# 5v-buck-regulator.net
KiCad netlist of a schematic drawn in EAGLE
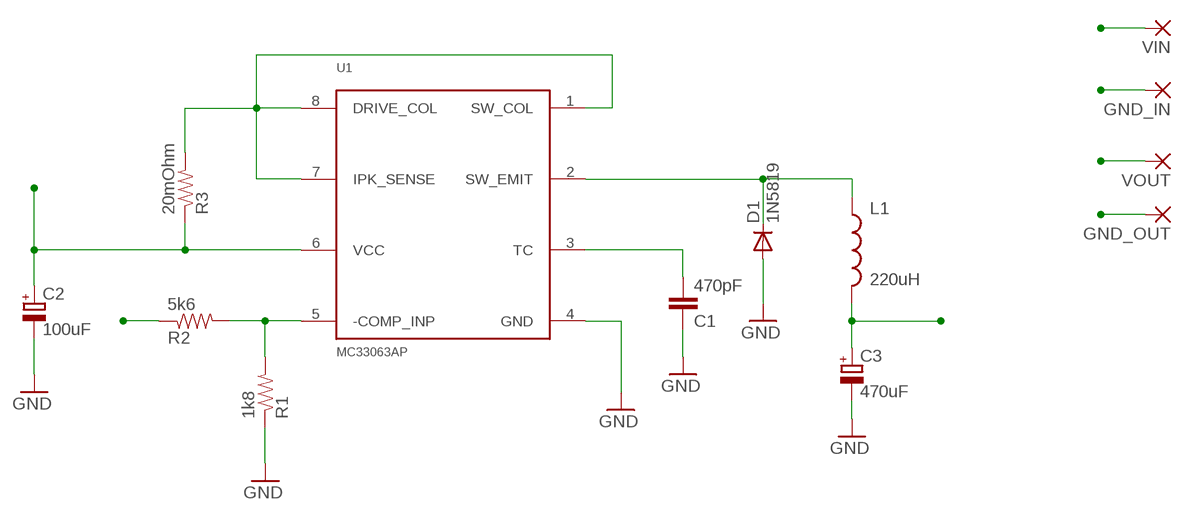
[diagram p0: schematic, sheet 1]

(export (version "E")
  (design (tool "Eeschema 10.0.6"))
  (components
    (comp (ref "C1")
      (value "470pF")
      (footprint "eagle-import:0805")
      (libsource (lib "eagle-import") (part "CAP0805"))
    )
    (comp (ref "C2")
      (value "100uF")
      (footprint "eagle-import:PANASONIC_C")
      (libsource (lib "eagle-import") (part "CPOL-EUC"))
    )
    (comp (ref "C3")
      (value "470uF")
      (footprint "eagle-import:PANASONIC_D")
      (libsource (lib "eagle-import") (part "CPOL-EUD"))
    )
    (comp (ref "D1")
      (value "1N5819")
      (footprint "eagle-import:SOD123")
      (libsource (lib "eagle-import") (part "MBR0520LT"))
    )
    (comp (ref "GND_IN")
      (value "WIREPAD2,54/0,8")
      (footprint "eagle-import:2,54_0,8")
      (libsource (lib "eagle-import") (part "WIREPAD2,54/0,8"))
    )
    (comp (ref "GND_OUT")
      (value "WIREPAD2,54/0,8")
      (footprint "eagle-import:2,54_0,8")
      (libsource (lib "eagle-import") (part "WIREPAD2,54/0,8"))
    )
    (comp (ref "L1")
      (value "220uH")
      (footprint "eagle-import:B82462G")
      (libsource (lib "eagle-import") (part "INDUCTOR-B82462G"))
    )
    (comp (ref "R1")
      (value "1k8")
      (footprint "eagle-import:0805")
      (libsource (lib "eagle-import") (part "RESISTOR0805-RES"))
    )
    (comp (ref "R2")
      (value "5k6")
      (footprint "eagle-import:0805")
      (libsource (lib "eagle-import") (part "RESISTOR0805-RES"))
    )
    (comp (ref "R3")
      (value "20mOhm")
      (footprint "eagle-import:R2010")
      (libsource (lib "eagle-import") (part "RESISTOR2010"))
    )
    (comp (ref "U1")
      (value "MC33063AP")
      (footprint "eagle-import:SOIC-8")
      (libsource (lib "eagle-import") (part "MC33063AMC34063A"))
    )
    (comp (ref "VIN")
      (value "WIREPAD2,54/0,8")
      (footprint "eagle-import:2,54_0,8")
      (libsource (lib "eagle-import") (part "WIREPAD2,54/0,8"))
    )
    (comp (ref "VOUT")
      (value "WIREPAD2,54/0,8")
      (footprint "eagle-import:2,54_0,8")
      (libsource (lib "eagle-import") (part "WIREPAD2,54/0,8"))
    )
  )
  (nets
    (net (code "1") (name "/VIN") (class "Default")
      (node (ref "C2") (pin "+") (pinfunction "+_+") (pintype "passive"))
      (node (ref "R3") (pin "1") (pinfunction "1_1") (pintype "passive"))
      (node (ref "U1") (pin "6") (pinfunction "VCC_6") (pintype "bidirectional"))
      (node (ref "VIN") (pin "1") (pinfunction "P_1") (pintype "passive"))
    )
    (net (code "2") (name "/VOUT") (class "Default")
      (node (ref "C3") (pin "+") (pinfunction "+_+") (pintype "passive"))
      (node (ref "L1") (pin "P$2") (pinfunction "2_P$2") (pintype "passive"))
      (node (ref "R2") (pin "1") (pinfunction "1_1") (pintype "passive"))
      (node (ref "VOUT") (pin "1") (pinfunction "P_1") (pintype "passive"))
    )
    (net (code "3") (name "GND") (class "Default")
      (node (ref "C1") (pin "1") (pinfunction "1_1") (pintype "passive"))
      (node (ref "C2") (pin "-") (pinfunction "-_-") (pintype "passive"))
      (node (ref "C3") (pin "-") (pinfunction "-_-") (pintype "passive"))
      (node (ref "D1") (pin "A") (pinfunction "A_A") (pintype "passive"))
      (node (ref "GND_IN") (pin "1") (pinfunction "P_1") (pintype "passive"))
      (node (ref "GND_OUT") (pin "1") (pinfunction "P_1") (pintype "passive"))
      (node (ref "R1") (pin "1") (pinfunction "1_1") (pintype "passive"))
      (node (ref "U1") (pin "4") (pinfunction "GND_4") (pintype "bidirectional"))
    )
    (net (code "4") (name "Net-(L1-1)") (class "Default")
      (node (ref "D1") (pin "C") (pinfunction "C_C") (pintype "passive"))
      (node (ref "L1") (pin "P$1") (pinfunction "1_P$1") (pintype "passive"))
      (node (ref "U1") (pin "2") (pinfunction "SW_EMIT_2") (pintype "bidirectional"))
    )
    (net (code "5") (name "Net-(U1--COMP_INP)") (class "Default")
      (node (ref "R1") (pin "2") (pinfunction "2_2") (pintype "passive"))
      (node (ref "R2") (pin "2") (pinfunction "2_2") (pintype "passive"))
      (node (ref "U1") (pin "5") (pinfunction "-COMP_INP_5") (pintype "bidirectional"))
    )
    (net (code "6") (name "Net-(U1-DRIVE_COL)") (class "Default")
      (node (ref "R3") (pin "2") (pinfunction "2_2") (pintype "passive"))
      (node (ref "U1") (pin "1") (pinfunction "SW_COL_1") (pintype "bidirectional"))
      (node (ref "U1") (pin "7") (pinfunction "IPK_SENSE_7") (pintype "bidirectional"))
      (node (ref "U1") (pin "8") (pinfunction "DRIVE_COL_8") (pintype "bidirectional"))
    )
    (net (code "7") (name "Net-(U1-TC)") (class "Default")
      (node (ref "C1") (pin "2") (pinfunction "2_2") (pintype "passive"))
      (node (ref "U1") (pin "3") (pinfunction "TC_3") (pintype "bidirectional"))
    )
  )
)
